# loop-rs232.net
KiCad netlist of a schematic drawn in EAGLE
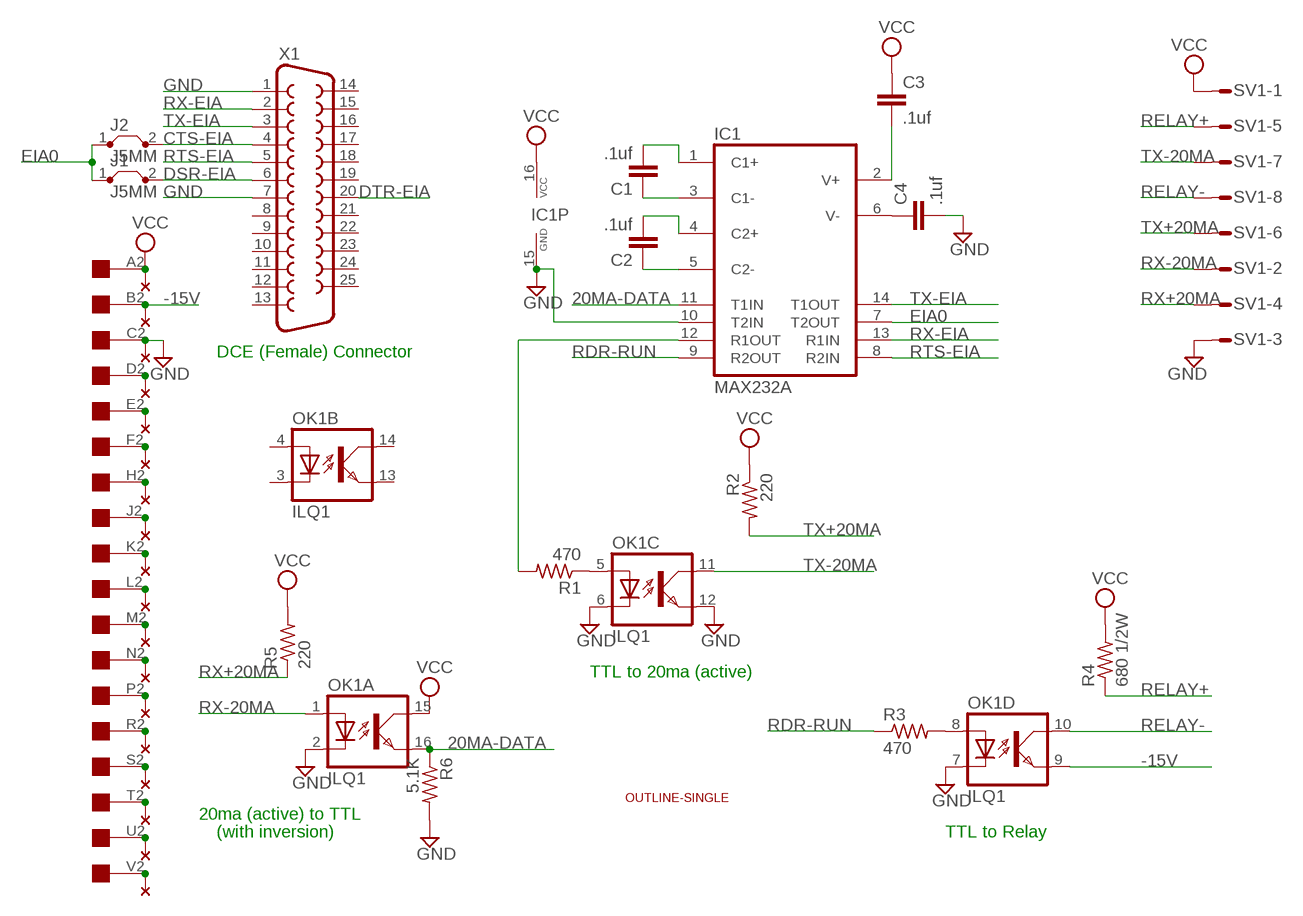
[diagram p0: schematic, sheet 1]

(export (version "E")
  (design (tool "Eeschema 10.0.6"))
  (components
    (comp (ref "C1")
      (value ".1uf")
      (footprint "eagle-import:C050-025X075")
      (libsource (lib "eagle-import") (part "C-EU050-025X075"))
    )
    (comp (ref "C2")
      (value ".1uf")
      (footprint "eagle-import:C050-025X075")
      (libsource (lib "eagle-import") (part "C-EU050-025X075"))
    )
    (comp (ref "C3")
      (value ".1uf")
      (footprint "eagle-import:C050-025X075")
      (libsource (lib "eagle-import") (part "C-EU050-025X075"))
    )
    (comp (ref "C4")
      (value ".1uf")
      (footprint "eagle-import:C050-025X075")
      (libsource (lib "eagle-import") (part "C-EU050-025X075"))
    )
    (comp (ref "IC1")
      (value "MAX232A")
      (footprint "eagle-import:DIL16")
      (fields (field (name "MF") "MAXIM") (field (name "MPN") "MAX232ACPE+"))
      (libsource (lib "eagle-import") (part "MAX232"))
    )
    (comp (ref "J1")
      (value "J5MM")
      (footprint "eagle-import:05")
      (libsource (lib "eagle-import") (part "J5MM"))
    )
    (comp (ref "J2")
      (value "J5MM")
      (footprint "eagle-import:05")
      (libsource (lib "eagle-import") (part "J5MM"))
    )
    (comp (ref "OK1")
      (value "ILQ1")
      (footprint "eagle-import:DIL16")
      (fields (field (name "MF") "VISHAY/TELEFUNKEN"))
      (libsource (lib "eagle-import") (part "ILQ1"))
    )
    (comp (ref "R1")
      (value "470")
      (footprint "eagle-import:0207_10")
      (libsource (lib "eagle-import") (part "R-US_0207/10"))
    )
    (comp (ref "R2")
      (value "220")
      (footprint "eagle-import:0207_10")
      (libsource (lib "eagle-import") (part "R-US_0207/10"))
    )
    (comp (ref "R3")
      (value "470")
      (footprint "eagle-import:0207_10")
      (libsource (lib "eagle-import") (part "R-US_0207/10"))
    )
    (comp (ref "R4")
      (value "680 1/2W")
      (footprint "eagle-import:0207_10")
      (libsource (lib "eagle-import") (part "R-US_0207/10"))
    )
    (comp (ref "R5")
      (value "220")
      (footprint "eagle-import:0207_10")
      (libsource (lib "eagle-import") (part "R-US_0207/10"))
    )
    (comp (ref "R6")
      (value "5.1K")
      (footprint "eagle-import:0207_10")
      (libsource (lib "eagle-import") (part "R-US_0207/10"))
    )
    (comp (ref "SV1")
      (value "S08P")
      (footprint "eagle-import:S08P")
      (libsource (lib "eagle-import") (part "S08P"))
    )
    (comp (ref "U$2")
      (value "EDGE-1")
      (footprint "eagle-import:EDGE-CON1")
      (libsource (lib "eagle-import") (part "EDGE-1"))
    )
    (comp (ref "U$3")
      (value "OUTLINE-SINGLE")
      (footprint "eagle-import:SINGLE")
      (libsource (lib "eagle-import") (part "OUTLINE-SINGLE"))
    )
    (comp (ref "U$4")
      (value "THRU-HOLE1")
      (footprint "eagle-import:THRU-HOLE1")
      (libsource (lib "eagle-import") (part "THRU-HOLE1"))
    )
    (comp (ref "X1")
      (value "F25H")
      (footprint "eagle-import:F25H")
      (libsource (lib "eagle-import") (part "F25H"))
    )
  )
  (nets
    (net (code "1") (name "/-15V") (class "Default")
      (node (ref "OK1") (pin "9") (pinfunction "EMIT_9") (pintype "passive"))
      (node (ref "U$2") (pin "B2") (pinfunction "1_B2") (pintype "bidirectional"))
      (node (ref "U$4") (pin "B2") (pinfunction "P$1_B2") (pintype "passive"))
    )
    (net (code "2") (name "/20MA-DATA") (class "Default")
      (node (ref "IC1") (pin "11") (pinfunction "T1IN_11") (pintype "input"))
      (node (ref "OK1") (pin "16") (pinfunction "EMIT_16") (pintype "passive"))
      (node (ref "R6") (pin "1") (pinfunction "1_1") (pintype "passive"))
    )
    (net (code "3") (name "/CTS-EIA") (class "Default")
      (node (ref "J2") (pin "2") (pinfunction "2_2") (pintype "passive"))
      (node (ref "X1") (pin "4") (pinfunction "4_4") (pintype "passive"))
    )
    (net (code "4") (name "/DSR-EIA") (class "Default")
      (node (ref "J1") (pin "2") (pinfunction "2_2") (pintype "passive"))
      (node (ref "X1") (pin "6") (pinfunction "6_6") (pintype "passive"))
    )
    (net (code "5") (name "/DTR-EIA") (class "Default")
      (node (ref "X1") (pin "20") (pinfunction "20_20") (pintype "passive"))
    )
    (net (code "6") (name "/EIA0") (class "Default")
      (node (ref "IC1") (pin "7") (pinfunction "T2OUT_7") (pintype "output"))
      (node (ref "J1") (pin "1") (pinfunction "1_1") (pintype "passive"))
      (node (ref "J2") (pin "1") (pinfunction "1_1") (pintype "passive"))
    )
    (net (code "7") (name "/RDR-RUN") (class "Default")
      (node (ref "IC1") (pin "9") (pinfunction "R2OUT_9") (pintype "output"))
      (node (ref "R3") (pin "1") (pinfunction "1_1") (pintype "passive"))
    )
    (net (code "8") (name "/RELAY+") (class "Default")
      (node (ref "R4") (pin "1") (pinfunction "1_1") (pintype "passive"))
      (node (ref "SV1") (pin "5") (pinfunction "S_5") (pintype "passive"))
    )
    (net (code "9") (name "/RELAY-") (class "Default")
      (node (ref "OK1") (pin "10") (pinfunction "COL_10") (pintype "passive"))
      (node (ref "SV1") (pin "8") (pinfunction "S_8") (pintype "passive"))
    )
    (net (code "10") (name "/RTS-EIA") (class "Default")
      (node (ref "IC1") (pin "8") (pinfunction "R2IN_8") (pintype "input"))
      (node (ref "X1") (pin "5") (pinfunction "5_5") (pintype "passive"))
    )
    (net (code "11") (name "/RX+20MA") (class "Default")
      (node (ref "R5") (pin "1") (pinfunction "1_1") (pintype "passive"))
      (node (ref "SV1") (pin "4") (pinfunction "S_4") (pintype "passive"))
    )
    (net (code "12") (name "/RX-20MA") (class "Default")
      (node (ref "OK1") (pin "1") (pinfunction "A_1") (pintype "passive"))
      (node (ref "SV1") (pin "2") (pinfunction "S_2") (pintype "passive"))
    )
    (net (code "13") (name "/RX-EIA") (class "Default")
      (node (ref "IC1") (pin "13") (pinfunction "R1IN_13") (pintype "input"))
      (node (ref "X1") (pin "2") (pinfunction "2_2") (pintype "passive"))
    )
    (net (code "14") (name "/TX+20MA") (class "Default")
      (node (ref "R2") (pin "2") (pinfunction "2_2") (pintype "passive"))
      (node (ref "SV1") (pin "6") (pinfunction "S_6") (pintype "passive"))
    )
    (net (code "15") (name "/TX-20MA") (class "Default")
      (node (ref "OK1") (pin "11") (pinfunction "COL_11") (pintype "passive"))
      (node (ref "SV1") (pin "7") (pinfunction "S_7") (pintype "passive"))
    )
    (net (code "16") (name "/TX-EIA") (class "Default")
      (node (ref "IC1") (pin "14") (pinfunction "T1OUT_14") (pintype "output"))
      (node (ref "X1") (pin "3") (pinfunction "3_3") (pintype "passive"))
    )
    (net (code "17") (name "GND") (class "Default")
      (node (ref "C4") (pin "2") (pinfunction "2_2") (pintype "passive"))
      (node (ref "IC1") (pin "10") (pinfunction "T2IN_10") (pintype "input"))
      (node (ref "IC1") (pin "15") (pinfunction "GND_15") (pintype "power_in"))
      (node (ref "OK1") (pin "12") (pinfunction "EMIT_12") (pintype "passive"))
      (node (ref "OK1") (pin "2") (pinfunction "C_2") (pintype "passive"))
      (node (ref "OK1") (pin "6") (pinfunction "C_6") (pintype "passive"))
      (node (ref "OK1") (pin "7") (pinfunction "C_7") (pintype "passive"))
      (node (ref "R6") (pin "2") (pinfunction "2_2") (pintype "passive"))
      (node (ref "SV1") (pin "3") (pinfunction "S_3") (pintype "passive"))
      (node (ref "U$2") (pin "C2") (pinfunction "1_C2") (pintype "bidirectional"))
      (node (ref "U$4") (pin "C2") (pinfunction "P$1_C2") (pintype "passive"))
      (node (ref "X1") (pin "1") (pinfunction "1_1") (pintype "passive"))
      (node (ref "X1") (pin "7") (pinfunction "7_7") (pintype "passive"))
    )
    (net (code "18") (name "Net-(IC1A-C1+)") (class "Default")
      (node (ref "C1") (pin "2") (pinfunction "2_2") (pintype "passive"))
      (node (ref "IC1") (pin "1") (pinfunction "C1+_1") (pintype "bidirectional"))
    )
    (net (code "19") (name "Net-(IC1A-C1-)") (class "Default")
      (node (ref "C1") (pin "1") (pinfunction "1_1") (pintype "passive"))
      (node (ref "IC1") (pin "3") (pinfunction "C1-_3") (pintype "bidirectional"))
    )
    (net (code "20") (name "Net-(IC1A-C2+)") (class "Default")
      (node (ref "C2") (pin "2") (pinfunction "2_2") (pintype "passive"))
      (node (ref "IC1") (pin "4") (pinfunction "C2+_4") (pintype "bidirectional"))
    )
    (net (code "21") (name "Net-(IC1A-C2-)") (class "Default")
      (node (ref "C2") (pin "1") (pinfunction "1_1") (pintype "passive"))
      (node (ref "IC1") (pin "5") (pinfunction "C2-_5") (pintype "bidirectional"))
    )
    (net (code "22") (name "Net-(IC1A-R1OUT)") (class "Default")
      (node (ref "IC1") (pin "12") (pinfunction "R1OUT_12") (pintype "output"))
      (node (ref "R1") (pin "2") (pinfunction "2_2") (pintype "passive"))
    )
    (net (code "23") (name "Net-(IC1A-V+)") (class "Default")
      (node (ref "C3") (pin "2") (pinfunction "2_2") (pintype "passive"))
      (node (ref "IC1") (pin "2") (pinfunction "V+_2") (pintype "bidirectional"))
    )
    (net (code "24") (name "Net-(IC1A-V-)") (class "Default")
      (node (ref "C4") (pin "1") (pinfunction "1_1") (pintype "passive"))
      (node (ref "IC1") (pin "6") (pinfunction "V-_6") (pintype "bidirectional"))
    )
    (net (code "25") (name "Net-(OK1C-A)") (class "Default")
      (node (ref "OK1") (pin "5") (pinfunction "A_5") (pintype "passive"))
      (node (ref "R1") (pin "1") (pinfunction "1_1") (pintype "passive"))
    )
    (net (code "26") (name "Net-(OK1D-A)") (class "Default")
      (node (ref "OK1") (pin "8") (pinfunction "A_8") (pintype "passive"))
      (node (ref "R3") (pin "2") (pinfunction "2_2") (pintype "passive"))
    )
    (net (code "27") (name "Net-(U$2D-1)") (class "Default")
      (node (ref "U$2") (pin "D2") (pinfunction "1_D2") (pintype "bidirectional"))
      (node (ref "U$4") (pin "D2") (pinfunction "P$1_D2") (pintype "passive"))
    )
    (net (code "28") (name "Net-(U$2E-1)") (class "Default")
      (node (ref "U$2") (pin "E2") (pinfunction "1_E2") (pintype "bidirectional"))
      (node (ref "U$4") (pin "E2") (pinfunction "P$1_E2") (pintype "passive"))
    )
    (net (code "29") (name "Net-(U$2F-1)") (class "Default")
      (node (ref "U$2") (pin "F2") (pinfunction "1_F2") (pintype "bidirectional"))
      (node (ref "U$4") (pin "F2") (pinfunction "P$1_F2") (pintype "passive"))
    )
    (net (code "30") (name "Net-(U$2G-1)") (class "Default")
      (node (ref "U$2") (pin "H2") (pinfunction "1_H2") (pintype "bidirectional"))
      (node (ref "U$4") (pin "H2") (pinfunction "P$1_H2") (pintype "passive"))
    )
    (net (code "31") (name "Net-(U$2H-1)") (class "Default")
      (node (ref "U$2") (pin "J2") (pinfunction "1_J2") (pintype "bidirectional"))
      (node (ref "U$4") (pin "J2") (pinfunction "P$1_J2") (pintype "passive"))
    )
    (net (code "32") (name "Net-(U$2I-1)") (class "Default")
      (node (ref "U$2") (pin "K2") (pinfunction "1_K2") (pintype "bidirectional"))
      (node (ref "U$4") (pin "K2") (pinfunction "P$1_K2") (pintype "passive"))
    )
    (net (code "33") (name "Net-(U$2J-1)") (class "Default")
      (node (ref "U$2") (pin "L2") (pinfunction "1_L2") (pintype "bidirectional"))
      (node (ref "U$4") (pin "L2") (pinfunction "P$1_L2") (pintype "passive"))
    )
    (net (code "34") (name "Net-(U$2K-1)") (class "Default")
      (node (ref "U$2") (pin "M2") (pinfunction "1_M2") (pintype "bidirectional"))
      (node (ref "U$4") (pin "M2") (pinfunction "P$1_M2") (pintype "passive"))
    )
    (net (code "35") (name "Net-(U$2L-1)") (class "Default")
      (node (ref "U$2") (pin "N2") (pinfunction "1_N2") (pintype "bidirectional"))
      (node (ref "U$4") (pin "N2") (pinfunction "P$1_N2") (pintype "passive"))
    )
    (net (code "36") (name "Net-(U$2M-1)") (class "Default")
      (node (ref "U$2") (pin "P2") (pinfunction "1_P2") (pintype "bidirectional"))
      (node (ref "U$4") (pin "P2") (pinfunction "P$1_P2") (pintype "passive"))
    )
    (net (code "37") (name "Net-(U$2N-1)") (class "Default")
      (node (ref "U$2") (pin "R2") (pinfunction "1_R2") (pintype "bidirectional"))
      (node (ref "U$4") (pin "R2") (pinfunction "P$1_R2") (pintype "passive"))
    )
    (net (code "38") (name "Net-(U$2O-1)") (class "Default")
      (node (ref "U$2") (pin "S2") (pinfunction "1_S2") (pintype "bidirectional"))
      (node (ref "U$4") (pin "S2") (pinfunction "P$1_S2") (pintype "passive"))
    )
    (net (code "39") (name "Net-(U$2P-1)") (class "Default")
      (node (ref "U$2") (pin "T2") (pinfunction "1_T2") (pintype "bidirectional"))
      (node (ref "U$4") (pin "T2") (pinfunction "P$1_T2") (pintype "passive"))
    )
    (net (code "40") (name "Net-(U$2Q-1)") (class "Default")
      (node (ref "U$2") (pin "U2") (pinfunction "1_U2") (pintype "bidirectional"))
      (node (ref "U$4") (pin "U2") (pinfunction "P$1_U2") (pintype "passive"))
    )
    (net (code "41") (name "Net-(U$2R-1)") (class "Default")
      (node (ref "U$2") (pin "V2") (pinfunction "1_V2") (pintype "bidirectional"))
      (node (ref "U$4") (pin "V2") (pinfunction "P$1_V2") (pintype "passive"))
    )
    (net (code "42") (name "VCC") (class "Default")
      (node (ref "C3") (pin "1") (pinfunction "1_1") (pintype "passive"))
      (node (ref "IC1") (pin "16") (pinfunction "VCC_16") (pintype "power_in"))
      (node (ref "OK1") (pin "15") (pinfunction "COL_15") (pintype "passive"))
      (node (ref "R2") (pin "1") (pinfunction "1_1") (pintype "passive"))
      (node (ref "R4") (pin "2") (pinfunction "2_2") (pintype "passive"))
      (node (ref "R5") (pin "2") (pinfunction "2_2") (pintype "passive"))
      (node (ref "SV1") (pin "1") (pinfunction "S_1") (pintype "passive"))
      (node (ref "U$2") (pin "A2") (pinfunction "1_A2") (pintype "bidirectional"))
      (node (ref "U$4") (pin "A2") (pinfunction "P$1_A2") (pintype "passive"))
    )
    (net (code "43") (name "unconnected-(OK1B-A-Pad4)") (class "Default")
      (node (ref "OK1") (pin "4") (pinfunction "A_4") (pintype "passive"))
    )
    (net (code "44") (name "unconnected-(OK1B-C-Pad3)") (class "Default")
      (node (ref "OK1") (pin "3") (pinfunction "C_3") (pintype "passive"))
    )
    (net (code "45") (name "unconnected-(OK1B-COL-Pad14)") (class "Default")
      (node (ref "OK1") (pin "14") (pinfunction "COL_14") (pintype "passive"))
    )
    (net (code "46") (name "unconnected-(OK1B-EMIT-Pad13)") (class "Default")
      (node (ref "OK1") (pin "13") (pinfunction "EMIT_13") (pintype "passive"))
    )
    (net (code "47") (name "unconnected-(X1-Pad8)") (class "Default")
      (node (ref "X1") (pin "8") (pinfunction "8_8") (pintype "passive"))
    )
    (net (code "48") (name "unconnected-(X1-Pad9)") (class "Default")
      (node (ref "X1") (pin "9") (pinfunction "9_9") (pintype "passive"))
    )
    (net (code "49") (name "unconnected-(X1-Pad10)") (class "Default")
      (node (ref "X1") (pin "10") (pinfunction "10_10") (pintype "passive"))
    )
    (net (code "50") (name "unconnected-(X1-Pad11)") (class "Default")
      (node (ref "X1") (pin "11") (pinfunction "11_11") (pintype "passive"))
    )
    (net (code "51") (name "unconnected-(X1-Pad12)") (class "Default")
      (node (ref "X1") (pin "12") (pinfunction "12_12") (pintype "passive"))
    )
    (net (code "52") (name "unconnected-(X1-Pad13)") (class "Default")
      (node (ref "X1") (pin "13") (pinfunction "13_13") (pintype "passive"))
    )
    (net (code "53") (name "unconnected-(X1-Pad14)") (class "Default")
      (node (ref "X1") (pin "14") (pinfunction "14_14") (pintype "passive"))
    )
    (net (code "54") (name "unconnected-(X1-Pad15)") (class "Default")
      (node (ref "X1") (pin "15") (pinfunction "15_15") (pintype "passive"))
    )
    (net (code "55") (name "unconnected-(X1-Pad16)") (class "Default")
      (node (ref "X1") (pin "16") (pinfunction "16_16") (pintype "passive"))
    )
    (net (code "56") (name "unconnected-(X1-Pad17)") (class "Default")
      (node (ref "X1") (pin "17") (pinfunction "17_17") (pintype "passive"))
    )
    (net (code "57") (name "unconnected-(X1-Pad18)") (class "Default")
      (node (ref "X1") (pin "18") (pinfunction "18_18") (pintype "passive"))
    )
    (net (code "58") (name "unconnected-(X1-Pad19)") (class "Default")
      (node (ref "X1") (pin "19") (pinfunction "19_19") (pintype "passive"))
    )
    (net (code "59") (name "unconnected-(X1-Pad21)") (class "Default")
      (node (ref "X1") (pin "21") (pinfunction "21_21") (pintype "passive"))
    )
    (net (code "60") (name "unconnected-(X1-Pad22)") (class "Default")
      (node (ref "X1") (pin "22") (pinfunction "22_22") (pintype "passive"))
    )
    (net (code "61") (name "unconnected-(X1-Pad23)") (class "Default")
      (node (ref "X1") (pin "23") (pinfunction "23_23") (pintype "passive"))
    )
    (net (code "62") (name "unconnected-(X1-Pad24)") (class "Default")
      (node (ref "X1") (pin "24") (pinfunction "24_24") (pintype "passive"))
    )
    (net (code "63") (name "unconnected-(X1-Pad25)") (class "Default")
      (node (ref "X1") (pin "25") (pinfunction "25_25") (pintype "passive"))
    )
  )
)
